# Affichage.net
KiCad netlist of a schematic drawn in Altium Designer
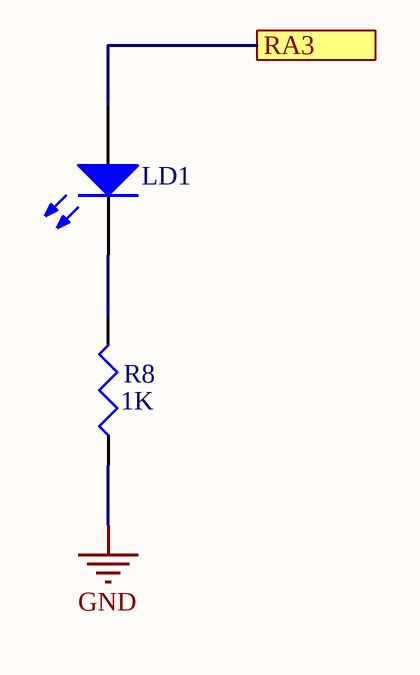
[diagram p0: Affichage.SchDoc]

(export (version "E")
  (design (tool "Eeschema 10.0.6"))
  (components
    (comp (ref "LD1")
      (value "LED2")
      (footprint "3.2X1.6X1.1")
      (description "Typical RED, GREEN, YELLOW, AMBER GaAs LED")
      (fields (field (name "PUBLISHER") "Altium Limited"))
      (libsource (lib "Miscellaneous Devices") (part "LED2"))
    )
    (comp (ref "R8")
      (value "1K")
      (footprint "J1-0603")
      (description "Resistor")
      (fields (field (name "Comment") "Res3") (field (name "PUBLISHER") "Altium Limited"))
      (libsource (lib "Miscellaneous Devices") (part "Res3"))
    )
  )
  (nets
    (net (code "1") (name "/RA3") (class "Default")
      (node (ref "LD1") (pin "1") (pinfunction "A_1") (pintype "passive"))
    )
    (net (code "2") (name "GND") (class "Default")
      (node (ref "R8") (pin "1") (pinfunction "1_1") (pintype "passive"))
    )
    (net (code "3") (name "Net-(LD1-K)") (class "Default")
      (node (ref "LD1") (pin "2") (pinfunction "K_2") (pintype "passive"))
      (node (ref "R8") (pin "2") (pinfunction "2_2") (pintype "passive"))
    )
  )
)
